# crossover.net
KiCad netlist of a schematic drawn in EAGLE
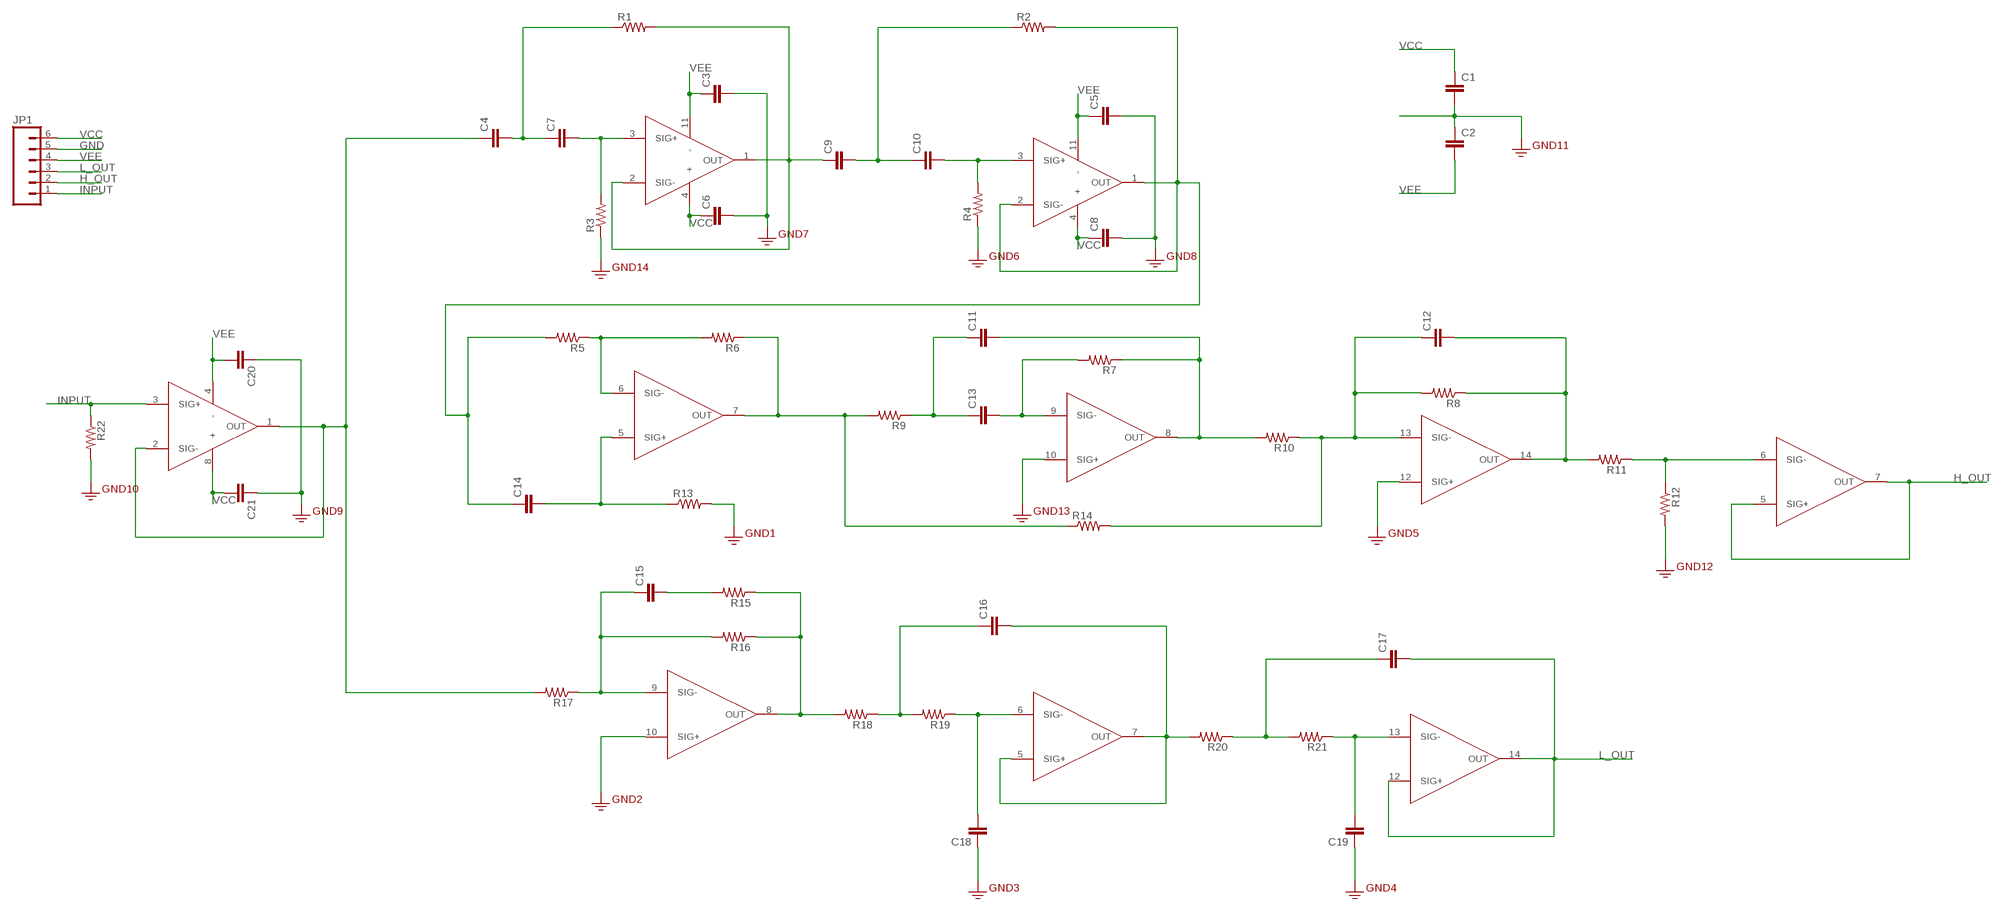
[diagram p0: schematic, sheet 1]

(export (version "E")
  (design (tool "Eeschema 10.0.6"))
  (components
    (comp (ref "C1")
      (value "CAPEZ")
      (footprint "eagle-import:CAP-PTH-SMALLEZ")
      (libsource (lib "eagle-import") (part "CAPEZ"))
    )
    (comp (ref "C2")
      (value "CAPEZ")
      (footprint "eagle-import:CAP-PTH-SMALLEZ")
      (libsource (lib "eagle-import") (part "CAPEZ"))
    )
    (comp (ref "C3")
      (value "CAPEZ")
      (footprint "eagle-import:CAP-PTH-SMALLEZ")
      (libsource (lib "eagle-import") (part "CAPEZ"))
    )
    (comp (ref "C4")
      (value "CAPEZ")
      (footprint "eagle-import:CAP-PTH-SMALLEZ")
      (libsource (lib "eagle-import") (part "CAPEZ"))
    )
    (comp (ref "C5")
      (value "CAPEZ")
      (footprint "eagle-import:CAP-PTH-SMALLEZ")
      (libsource (lib "eagle-import") (part "CAPEZ"))
    )
    (comp (ref "C6")
      (value "CAPEZ")
      (footprint "eagle-import:CAP-PTH-SMALLEZ")
      (libsource (lib "eagle-import") (part "CAPEZ"))
    )
    (comp (ref "C7")
      (value "CAPEZ")
      (footprint "eagle-import:CAP-PTH-SMALLEZ")
      (libsource (lib "eagle-import") (part "CAPEZ"))
    )
    (comp (ref "C8")
      (value "CAPEZ")
      (footprint "eagle-import:CAP-PTH-SMALLEZ")
      (libsource (lib "eagle-import") (part "CAPEZ"))
    )
    (comp (ref "C9")
      (value "CAPEZ")
      (footprint "eagle-import:CAP-PTH-SMALLEZ")
      (libsource (lib "eagle-import") (part "CAPEZ"))
    )
    (comp (ref "C10")
      (value "CAPEZ")
      (footprint "eagle-import:CAP-PTH-SMALLEZ")
      (libsource (lib "eagle-import") (part "CAPEZ"))
    )
    (comp (ref "C11")
      (value "CAPEZ")
      (footprint "eagle-import:CAP-PTH-SMALLEZ")
      (libsource (lib "eagle-import") (part "CAPEZ"))
    )
    (comp (ref "C12")
      (value "CAPEZ")
      (footprint "eagle-import:CAP-PTH-SMALLEZ")
      (libsource (lib "eagle-import") (part "CAPEZ"))
    )
    (comp (ref "C13")
      (value "CAPEZ")
      (footprint "eagle-import:CAP-PTH-SMALLEZ")
      (libsource (lib "eagle-import") (part "CAPEZ"))
    )
    (comp (ref "C14")
      (value "CAPEZ")
      (footprint "eagle-import:CAP-PTH-SMALLEZ")
      (libsource (lib "eagle-import") (part "CAPEZ"))
    )
    (comp (ref "C15")
      (value "CAPEZ")
      (footprint "eagle-import:CAP-PTH-SMALLEZ")
      (libsource (lib "eagle-import") (part "CAPEZ"))
    )
    (comp (ref "C16")
      (value "CAPEZ")
      (footprint "eagle-import:CAP-PTH-SMALLEZ")
      (libsource (lib "eagle-import") (part "CAPEZ"))
    )
    (comp (ref "C17")
      (value "CAPEZ")
      (footprint "eagle-import:CAP-PTH-SMALLEZ")
      (libsource (lib "eagle-import") (part "CAPEZ"))
    )
    (comp (ref "C18")
      (value "CAPEZ")
      (footprint "eagle-import:CAP-PTH-SMALLEZ")
      (libsource (lib "eagle-import") (part "CAPEZ"))
    )
    (comp (ref "C19")
      (value "CAPEZ")
      (footprint "eagle-import:CAP-PTH-SMALLEZ")
      (libsource (lib "eagle-import") (part "CAPEZ"))
    )
    (comp (ref "C20")
      (value "CAPEZ")
      (footprint "eagle-import:CAP-PTH-SMALLEZ")
      (libsource (lib "eagle-import") (part "CAPEZ"))
    )
    (comp (ref "C21")
      (value "CAPEZ")
      (footprint "eagle-import:CAP-PTH-SMALLEZ")
      (libsource (lib "eagle-import") (part "CAPEZ"))
    )
    (comp (ref "JP1")
      (value "M06SIP")
      (footprint "eagle-import:1X06")
      (libsource (lib "eagle-import") (part "M06SIP"))
    )
    (comp (ref "R1")
      (value "RESISTORPTH-1/4W")
      (footprint "eagle-import:AXIAL-0.4")
      (libsource (lib "eagle-import") (part "RESISTORPTH-1/4W"))
    )
    (comp (ref "R2")
      (value "RESISTORPTH-1/4W")
      (footprint "eagle-import:AXIAL-0.4")
      (libsource (lib "eagle-import") (part "RESISTORPTH-1/4W"))
    )
    (comp (ref "R3")
      (value "RESISTORPTH-1/4W")
      (footprint "eagle-import:AXIAL-0.4")
      (libsource (lib "eagle-import") (part "RESISTORPTH-1/4W"))
    )
    (comp (ref "R4")
      (value "RESISTORPTH-1/4W")
      (footprint "eagle-import:AXIAL-0.4")
      (libsource (lib "eagle-import") (part "RESISTORPTH-1/4W"))
    )
    (comp (ref "R5")
      (value "RESISTORPTH-1/4W")
      (footprint "eagle-import:AXIAL-0.4")
      (libsource (lib "eagle-import") (part "RESISTORPTH-1/4W"))
    )
    (comp (ref "R6")
      (value "RESISTORPTH-1/4W")
      (footprint "eagle-import:AXIAL-0.4")
      (libsource (lib "eagle-import") (part "RESISTORPTH-1/4W"))
    )
    (comp (ref "R7")
      (value "RESISTORPTH-1/4W")
      (footprint "eagle-import:AXIAL-0.4")
      (libsource (lib "eagle-import") (part "RESISTORPTH-1/4W"))
    )
    (comp (ref "R8")
      (value "RESISTORPTH-1/4W")
      (footprint "eagle-import:AXIAL-0.4")
      (libsource (lib "eagle-import") (part "RESISTORPTH-1/4W"))
    )
    (comp (ref "R9")
      (value "RESISTORPTH-1/4W")
      (footprint "eagle-import:AXIAL-0.4")
      (libsource (lib "eagle-import") (part "RESISTORPTH-1/4W"))
    )
    (comp (ref "R10")
      (value "RESISTORPTH-1/4W")
      (footprint "eagle-import:AXIAL-0.4")
      (libsource (lib "eagle-import") (part "RESISTORPTH-1/4W"))
    )
    (comp (ref "R11")
      (value "RESISTORPTH-1/4W")
      (footprint "eagle-import:AXIAL-0.4")
      (libsource (lib "eagle-import") (part "RESISTORPTH-1/4W"))
    )
    (comp (ref "R12")
      (value "RESISTORPTH-1/4W")
      (footprint "eagle-import:AXIAL-0.4")
      (libsource (lib "eagle-import") (part "RESISTORPTH-1/4W"))
    )
    (comp (ref "R13")
      (value "RESISTORPTH-1/4W")
      (footprint "eagle-import:AXIAL-0.4")
      (libsource (lib "eagle-import") (part "RESISTORPTH-1/4W"))
    )
    (comp (ref "R14")
      (value "RESISTORPTH-1/4W")
      (footprint "eagle-import:AXIAL-0.4")
      (libsource (lib "eagle-import") (part "RESISTORPTH-1/4W"))
    )
    (comp (ref "R15")
      (value "RESISTORPTH-1/4W")
      (footprint "eagle-import:AXIAL-0.4")
      (libsource (lib "eagle-import") (part "RESISTORPTH-1/4W"))
    )
    (comp (ref "R16")
      (value "RESISTORPTH-1/4W")
      (footprint "eagle-import:AXIAL-0.4")
      (libsource (lib "eagle-import") (part "RESISTORPTH-1/4W"))
    )
    (comp (ref "R17")
      (value "RESISTORPTH-1/4W")
      (footprint "eagle-import:AXIAL-0.4")
      (libsource (lib "eagle-import") (part "RESISTORPTH-1/4W"))
    )
    (comp (ref "R18")
      (value "RESISTORPTH-1/4W")
      (footprint "eagle-import:AXIAL-0.4")
      (libsource (lib "eagle-import") (part "RESISTORPTH-1/4W"))
    )
    (comp (ref "R19")
      (value "RESISTORPTH-1/4W")
      (footprint "eagle-import:AXIAL-0.4")
      (libsource (lib "eagle-import") (part "RESISTORPTH-1/4W"))
    )
    (comp (ref "R20")
      (value "RESISTORPTH-1/4W")
      (footprint "eagle-import:AXIAL-0.4")
      (libsource (lib "eagle-import") (part "RESISTORPTH-1/4W"))
    )
    (comp (ref "R21")
      (value "RESISTORPTH-1/4W")
      (footprint "eagle-import:AXIAL-0.4")
      (libsource (lib "eagle-import") (part "RESISTORPTH-1/4W"))
    )
    (comp (ref "R22")
      (value "RESISTORPTH-1/4W")
      (footprint "eagle-import:AXIAL-0.4")
      (libsource (lib "eagle-import") (part "RESISTORPTH-1/4W"))
    )
    (comp (ref "U$1")
      (value "OPA1604STANDARD")
      (footprint "eagle-import:SOIC-14")
      (libsource (lib "eagle-import") (part "OPA1604STANDARD"))
    )
    (comp (ref "U$2")
      (value "OPA1604STANDARD")
      (footprint "eagle-import:SOIC-14")
      (libsource (lib "eagle-import") (part "OPA1604STANDARD"))
    )
    (comp (ref "U$3")
      (value "OPA1602")
      (footprint "eagle-import:SOIC8")
      (libsource (lib "eagle-import") (part "OPA1602"))
    )
  )
  (nets
    (net (code "1") (name "/H_OUT") (class "Default")
      (node (ref "JP1") (pin "2") (pinfunction "2_2") (pintype "passive"))
      (node (ref "U$3") (pin "5") (pinfunction "SIG+_5") (pintype "bidirectional"))
      (node (ref "U$3") (pin "7") (pinfunction "OUT_7") (pintype "bidirectional"))
    )
    (net (code "2") (name "/INPUT") (class "Default")
      (node (ref "JP1") (pin "1") (pinfunction "1_1") (pintype "passive"))
      (node (ref "R22") (pin "P$1") (pinfunction "1_P$1") (pintype "passive"))
      (node (ref "U$3") (pin "3") (pinfunction "SIG+_3") (pintype "bidirectional"))
    )
    (net (code "3") (name "/L_OUT") (class "Default")
      (node (ref "C17") (pin "2") (pinfunction "2_2") (pintype "passive"))
      (node (ref "JP1") (pin "3") (pinfunction "3_3") (pintype "passive"))
      (node (ref "U$1") (pin "12") (pinfunction "SIG+_12") (pintype "bidirectional"))
      (node (ref "U$1") (pin "14") (pinfunction "OUT_14") (pintype "bidirectional"))
    )
    (net (code "4") (name "/VCC") (class "Default")
      (node (ref "C1") (pin "1") (pinfunction "1_1") (pintype "passive"))
      (node (ref "C21") (pin "2") (pinfunction "2_2") (pintype "passive"))
      (node (ref "C6") (pin "1") (pinfunction "1_1") (pintype "passive"))
      (node (ref "C8") (pin "1") (pinfunction "1_1") (pintype "passive"))
      (node (ref "JP1") (pin "6") (pinfunction "6_6") (pintype "passive"))
      (node (ref "U$1") (pin "4") (pinfunction "+_4") (pintype "bidirectional"))
      (node (ref "U$2") (pin "4") (pinfunction "+_4") (pintype "bidirectional"))
      (node (ref "U$3") (pin "8") (pinfunction "+_8") (pintype "bidirectional"))
    )
    (net (code "5") (name "/VEE") (class "Default")
      (node (ref "C2") (pin "2") (pinfunction "2_2") (pintype "passive"))
      (node (ref "C20") (pin "2") (pinfunction "2_2") (pintype "passive"))
      (node (ref "C3") (pin "1") (pinfunction "1_1") (pintype "passive"))
      (node (ref "C5") (pin "1") (pinfunction "1_1") (pintype "passive"))
      (node (ref "JP1") (pin "4") (pinfunction "4_4") (pintype "passive"))
      (node (ref "U$1") (pin "11") (pinfunction "-_11") (pintype "bidirectional"))
      (node (ref "U$2") (pin "11") (pinfunction "-_11") (pintype "bidirectional"))
      (node (ref "U$3") (pin "4") (pinfunction "-_4") (pintype "bidirectional"))
    )
    (net (code "6") (name "GND2") (class "Default")
      (node (ref "C1") (pin "2") (pinfunction "2_2") (pintype "passive"))
      (node (ref "C18") (pin "1") (pinfunction "1_1") (pintype "passive"))
      (node (ref "C19") (pin "1") (pinfunction "1_1") (pintype "passive"))
      (node (ref "C2") (pin "1") (pinfunction "1_1") (pintype "passive"))
      (node (ref "C20") (pin "1") (pinfunction "1_1") (pintype "passive"))
      (node (ref "C21") (pin "1") (pinfunction "1_1") (pintype "passive"))
      (node (ref "C3") (pin "2") (pinfunction "2_2") (pintype "passive"))
      (node (ref "C5") (pin "2") (pinfunction "2_2") (pintype "passive"))
      (node (ref "C6") (pin "2") (pinfunction "2_2") (pintype "passive"))
      (node (ref "C8") (pin "2") (pinfunction "2_2") (pintype "passive"))
      (node (ref "JP1") (pin "5") (pinfunction "5_5") (pintype "passive"))
      (node (ref "R12") (pin "P$2") (pinfunction "2_P$2") (pintype "passive"))
      (node (ref "R13") (pin "P$2") (pinfunction "2_P$2") (pintype "passive"))
      (node (ref "R22") (pin "P$2") (pinfunction "2_P$2") (pintype "passive"))
      (node (ref "R3") (pin "P$1") (pinfunction "1_P$1") (pintype "passive"))
      (node (ref "R4") (pin "P$1") (pinfunction "1_P$1") (pintype "passive"))
      (node (ref "U$1") (pin "10") (pinfunction "SIG+_10") (pintype "bidirectional"))
      (node (ref "U$2") (pin "10") (pinfunction "SIG+_10") (pintype "bidirectional"))
      (node (ref "U$2") (pin "12") (pinfunction "SIG+_12") (pintype "bidirectional"))
    )
    (net (code "7") (name "Net-(R1-1)") (class "Default")
      (node (ref "C4") (pin "2") (pinfunction "2_2") (pintype "passive"))
      (node (ref "C7") (pin "1") (pinfunction "1_1") (pintype "passive"))
      (node (ref "R1") (pin "P$1") (pinfunction "1_P$1") (pintype "passive"))
    )
    (net (code "8") (name "Net-(R1-2)") (class "Default")
      (node (ref "C9") (pin "1") (pinfunction "1_1") (pintype "passive"))
      (node (ref "R1") (pin "P$2") (pinfunction "2_P$2") (pintype "passive"))
      (node (ref "U$1") (pin "1") (pinfunction "OUT_1") (pintype "bidirectional"))
      (node (ref "U$1") (pin "2") (pinfunction "SIG-_2") (pintype "bidirectional"))
    )
    (net (code "9") (name "Net-(R2-1)") (class "Default")
      (node (ref "C10") (pin "1") (pinfunction "1_1") (pintype "passive"))
      (node (ref "C9") (pin "2") (pinfunction "2_2") (pintype "passive"))
      (node (ref "R2") (pin "P$1") (pinfunction "1_P$1") (pintype "passive"))
    )
    (net (code "10") (name "Net-(R2-2)") (class "Default")
      (node (ref "C14") (pin "1") (pinfunction "1_1") (pintype "passive"))
      (node (ref "R2") (pin "P$2") (pinfunction "2_P$2") (pintype "passive"))
      (node (ref "R5") (pin "P$2") (pinfunction "2_P$2") (pintype "passive"))
      (node (ref "U$2") (pin "1") (pinfunction "OUT_1") (pintype "bidirectional"))
      (node (ref "U$2") (pin "2") (pinfunction "SIG-_2") (pintype "bidirectional"))
    )
    (net (code "11") (name "Net-(R3-2)") (class "Default")
      (node (ref "C7") (pin "2") (pinfunction "2_2") (pintype "passive"))
      (node (ref "R3") (pin "P$2") (pinfunction "2_P$2") (pintype "passive"))
      (node (ref "U$1") (pin "3") (pinfunction "SIG+_3") (pintype "bidirectional"))
    )
    (net (code "12") (name "Net-(R4-2)") (class "Default")
      (node (ref "C10") (pin "2") (pinfunction "2_2") (pintype "passive"))
      (node (ref "R4") (pin "P$2") (pinfunction "2_P$2") (pintype "passive"))
      (node (ref "U$2") (pin "3") (pinfunction "SIG+_3") (pintype "bidirectional"))
    )
    (net (code "13") (name "Net-(R5-1)") (class "Default")
      (node (ref "R5") (pin "P$1") (pinfunction "1_P$1") (pintype "passive"))
      (node (ref "R6") (pin "P$2") (pinfunction "2_P$2") (pintype "passive"))
      (node (ref "U$2") (pin "6") (pinfunction "SIG-_6") (pintype "bidirectional"))
    )
    (net (code "14") (name "Net-(R7-2)") (class "Default")
      (node (ref "C13") (pin "2") (pinfunction "2_2") (pintype "passive"))
      (node (ref "R7") (pin "P$2") (pinfunction "2_P$2") (pintype "passive"))
      (node (ref "U$2") (pin "9") (pinfunction "SIG-_9") (pintype "bidirectional"))
    )
    (net (code "15") (name "Net-(R9-1)") (class "Default")
      (node (ref "C11") (pin "1") (pinfunction "1_1") (pintype "passive"))
      (node (ref "C13") (pin "1") (pinfunction "1_1") (pintype "passive"))
      (node (ref "R9") (pin "P$1") (pinfunction "1_P$1") (pintype "passive"))
    )
    (net (code "16") (name "Net-(R10-1)") (class "Default")
      (node (ref "C12") (pin "1") (pinfunction "1_1") (pintype "passive"))
      (node (ref "R10") (pin "P$1") (pinfunction "1_P$1") (pintype "passive"))
      (node (ref "R14") (pin "P$2") (pinfunction "2_P$2") (pintype "passive"))
      (node (ref "R8") (pin "P$2") (pinfunction "2_P$2") (pintype "passive"))
      (node (ref "U$2") (pin "13") (pinfunction "SIG-_13") (pintype "bidirectional"))
    )
    (net (code "17") (name "Net-(R10-2)") (class "Default")
      (node (ref "C11") (pin "2") (pinfunction "2_2") (pintype "passive"))
      (node (ref "R10") (pin "P$2") (pinfunction "2_P$2") (pintype "passive"))
      (node (ref "R7") (pin "P$1") (pinfunction "1_P$1") (pintype "passive"))
      (node (ref "U$2") (pin "8") (pinfunction "OUT_8") (pintype "bidirectional"))
    )
    (net (code "18") (name "Net-(R11-1)") (class "Default")
      (node (ref "R11") (pin "P$1") (pinfunction "1_P$1") (pintype "passive"))
      (node (ref "R12") (pin "P$1") (pinfunction "1_P$1") (pintype "passive"))
      (node (ref "U$3") (pin "6") (pinfunction "SIG-_6") (pintype "bidirectional"))
    )
    (net (code "19") (name "Net-(R11-2)") (class "Default")
      (node (ref "C12") (pin "2") (pinfunction "2_2") (pintype "passive"))
      (node (ref "R11") (pin "P$2") (pinfunction "2_P$2") (pintype "passive"))
      (node (ref "R8") (pin "P$1") (pinfunction "1_P$1") (pintype "passive"))
      (node (ref "U$2") (pin "14") (pinfunction "OUT_14") (pintype "bidirectional"))
    )
    (net (code "20") (name "Net-(R13-1)") (class "Default")
      (node (ref "C14") (pin "2") (pinfunction "2_2") (pintype "passive"))
      (node (ref "R13") (pin "P$1") (pinfunction "1_P$1") (pintype "passive"))
      (node (ref "U$2") (pin "5") (pinfunction "SIG+_5") (pintype "bidirectional"))
    )
    (net (code "21") (name "Net-(R14-1)") (class "Default")
      (node (ref "R14") (pin "P$1") (pinfunction "1_P$1") (pintype "passive"))
      (node (ref "R6") (pin "P$1") (pinfunction "1_P$1") (pintype "passive"))
      (node (ref "R9") (pin "P$2") (pinfunction "2_P$2") (pintype "passive"))
      (node (ref "U$2") (pin "7") (pinfunction "OUT_7") (pintype "bidirectional"))
    )
    (net (code "22") (name "Net-(R15-1)") (class "Default")
      (node (ref "R15") (pin "P$1") (pinfunction "1_P$1") (pintype "passive"))
      (node (ref "R16") (pin "P$1") (pinfunction "1_P$1") (pintype "passive"))
      (node (ref "R18") (pin "P$2") (pinfunction "2_P$2") (pintype "passive"))
      (node (ref "U$1") (pin "8") (pinfunction "OUT_8") (pintype "bidirectional"))
    )
    (net (code "23") (name "Net-(R15-2)") (class "Default")
      (node (ref "C15") (pin "2") (pinfunction "2_2") (pintype "passive"))
      (node (ref "R15") (pin "P$2") (pinfunction "2_P$2") (pintype "passive"))
    )
    (net (code "24") (name "Net-(R16-2)") (class "Default")
      (node (ref "C15") (pin "1") (pinfunction "1_1") (pintype "passive"))
      (node (ref "R16") (pin "P$2") (pinfunction "2_P$2") (pintype "passive"))
      (node (ref "R17") (pin "P$1") (pinfunction "1_P$1") (pintype "passive"))
      (node (ref "U$1") (pin "9") (pinfunction "SIG-_9") (pintype "bidirectional"))
    )
    (net (code "25") (name "Net-(R17-2)") (class "Default")
      (node (ref "C4") (pin "1") (pinfunction "1_1") (pintype "passive"))
      (node (ref "R17") (pin "P$2") (pinfunction "2_P$2") (pintype "passive"))
      (node (ref "U$3") (pin "1") (pinfunction "OUT_1") (pintype "bidirectional"))
      (node (ref "U$3") (pin "2") (pinfunction "SIG-_2") (pintype "bidirectional"))
    )
    (net (code "26") (name "Net-(R18-1)") (class "Default")
      (node (ref "C16") (pin "1") (pinfunction "1_1") (pintype "passive"))
      (node (ref "R18") (pin "P$1") (pinfunction "1_P$1") (pintype "passive"))
      (node (ref "R19") (pin "P$2") (pinfunction "2_P$2") (pintype "passive"))
    )
    (net (code "27") (name "Net-(R19-1)") (class "Default")
      (node (ref "C18") (pin "2") (pinfunction "2_2") (pintype "passive"))
      (node (ref "R19") (pin "P$1") (pinfunction "1_P$1") (pintype "passive"))
      (node (ref "U$1") (pin "6") (pinfunction "SIG-_6") (pintype "bidirectional"))
    )
    (net (code "28") (name "Net-(R20-1)") (class "Default")
      (node (ref "C17") (pin "1") (pinfunction "1_1") (pintype "passive"))
      (node (ref "R20") (pin "P$1") (pinfunction "1_P$1") (pintype "passive"))
      (node (ref "R21") (pin "P$2") (pinfunction "2_P$2") (pintype "passive"))
    )
    (net (code "29") (name "Net-(R20-2)") (class "Default")
      (node (ref "C16") (pin "2") (pinfunction "2_2") (pintype "passive"))
      (node (ref "R20") (pin "P$2") (pinfunction "2_P$2") (pintype "passive"))
      (node (ref "U$1") (pin "5") (pinfunction "SIG+_5") (pintype "bidirectional"))
      (node (ref "U$1") (pin "7") (pinfunction "OUT_7") (pintype "bidirectional"))
    )
    (net (code "30") (name "Net-(R21-1)") (class "Default")
      (node (ref "C19") (pin "2") (pinfunction "2_2") (pintype "passive"))
      (node (ref "R21") (pin "P$1") (pinfunction "1_P$1") (pintype "passive"))
      (node (ref "U$1") (pin "13") (pinfunction "SIG-_13") (pintype "bidirectional"))
    )
  )
)
